# DRV8825.net
KiCad netlist of a schematic drawn in EAGLE
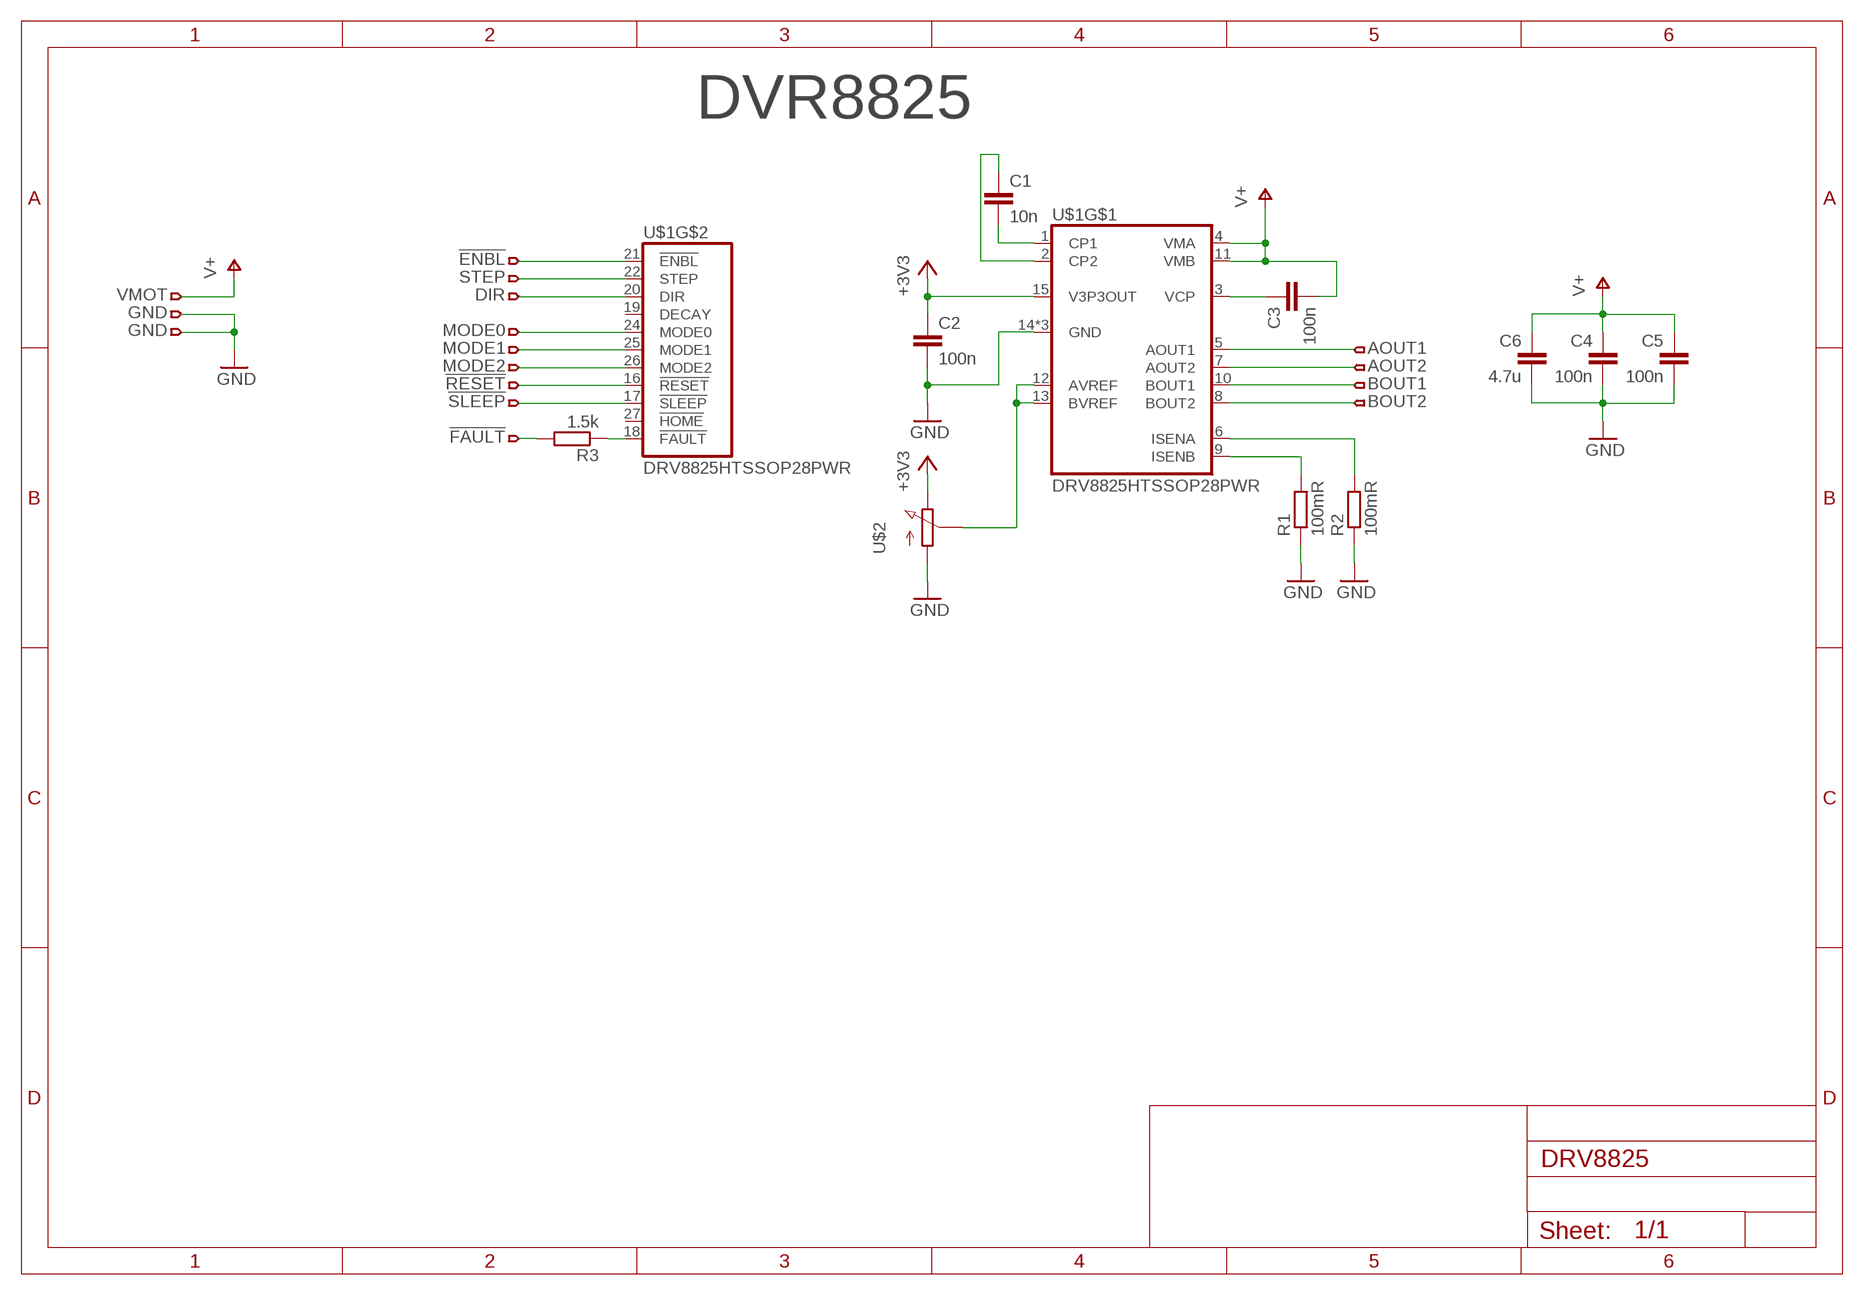
[diagram p0: schematic, sheet 1]

(export (version "E")
  (design (tool "Eeschema 10.0.6"))
  (components
    (comp (ref "C1")
      (value "10n")
      (footprint "eagle-import:C0603")
      (libsource (lib "eagle-import") (part "C-EUC0603"))
    )
    (comp (ref "C2")
      (value "100n")
      (footprint "eagle-import:C0603")
      (libsource (lib "eagle-import") (part "C-EUC0603"))
    )
    (comp (ref "C3")
      (value "100n")
      (footprint "eagle-import:C0603")
      (libsource (lib "eagle-import") (part "C-EUC0603"))
    )
    (comp (ref "C4")
      (value "100n")
      (footprint "eagle-import:C0603")
      (libsource (lib "eagle-import") (part "C-EUC0603"))
    )
    (comp (ref "C5")
      (value "100n")
      (footprint "eagle-import:C0603")
      (libsource (lib "eagle-import") (part "C-EUC0603"))
    )
    (comp (ref "C6")
      (value "4.7u")
      (footprint "eagle-import:C0603")
      (libsource (lib "eagle-import") (part "C-EUC0603"))
    )
    (comp (ref "JP3")
      (value "AOUT1")
      (footprint "eagle-import:1X01")
      (libsource (lib "eagle-import") (part "PINHD-1X1_2.54"))
    )
    (comp (ref "JP4")
      (value "AOUT2")
      (footprint "eagle-import:1X01")
      (libsource (lib "eagle-import") (part "PINHD-1X1_2.54"))
    )
    (comp (ref "JP5")
      (value "BOUT1")
      (footprint "eagle-import:1X01")
      (libsource (lib "eagle-import") (part "PINHD-1X1_2.54"))
    )
    (comp (ref "JP6")
      (value "BOUT2")
      (footprint "eagle-import:1X01")
      (libsource (lib "eagle-import") (part "PINHD-1X1_2.54"))
    )
    (comp (ref "JP7")
      (value "!ENBL")
      (footprint "eagle-import:1X01")
      (libsource (lib "eagle-import") (part "PINHD-1X1_2.54"))
    )
    (comp (ref "JP8")
      (value "STEP")
      (footprint "eagle-import:1X01")
      (libsource (lib "eagle-import") (part "PINHD-1X1_2.54"))
    )
    (comp (ref "JP9")
      (value "DIR")
      (footprint "eagle-import:1X01")
      (libsource (lib "eagle-import") (part "PINHD-1X1_2.54"))
    )
    (comp (ref "JP10")
      (value "VMOT")
      (footprint "eagle-import:1X01")
      (libsource (lib "eagle-import") (part "PINHD-1X1_2.54"))
    )
    (comp (ref "JP11")
      (value "MODE0")
      (footprint "eagle-import:1X01")
      (libsource (lib "eagle-import") (part "PINHD-1X1_2.54"))
    )
    (comp (ref "JP12")
      (value "MODE1")
      (footprint "eagle-import:1X01")
      (libsource (lib "eagle-import") (part "PINHD-1X1_2.54"))
    )
    (comp (ref "JP13")
      (value "MODE2")
      (footprint "eagle-import:1X01")
      (libsource (lib "eagle-import") (part "PINHD-1X1_2.54"))
    )
    (comp (ref "JP14")
      (value "!RESET")
      (footprint "eagle-import:1X01")
      (libsource (lib "eagle-import") (part "PINHD-1X1_2.54"))
    )
    (comp (ref "JP15")
      (value "!SLEEP")
      (footprint "eagle-import:1X01")
      (libsource (lib "eagle-import") (part "PINHD-1X1_2.54"))
    )
    (comp (ref "JP16")
      (value "GND")
      (footprint "eagle-import:1X01")
      (libsource (lib "eagle-import") (part "PINHD-1X1_2.54"))
    )
    (comp (ref "JP17")
      (value "!FAULT")
      (footprint "eagle-import:1X01")
      (libsource (lib "eagle-import") (part "PINHD-1X1_2.54"))
    )
    (comp (ref "JP18")
      (value "GND")
      (footprint "eagle-import:1X01")
      (libsource (lib "eagle-import") (part "PINHD-1X1_2.54"))
    )
    (comp (ref "R1")
      (value "100mR")
      (footprint "eagle-import:R0603")
      (libsource (lib "eagle-import") (part "R-EU_R0603"))
    )
    (comp (ref "R2")
      (value "100mR")
      (footprint "eagle-import:R0603")
      (libsource (lib "eagle-import") (part "R-EU_R0603"))
    )
    (comp (ref "R3")
      (value "1.5k")
      (footprint "eagle-import:R0603")
      (libsource (lib "eagle-import") (part "R-EU_R0603"))
    )
    (comp (ref "U$1")
      (value "DRV8825HTSSOP28PWR")
      (footprint "eagle-import:HTSSOP28PWP")
      (libsource (lib "eagle-import") (part "DRV8825HTSSOP28PWR"))
    )
    (comp (ref "U$2")
      (value "POT-PVZ3A")
      (footprint "eagle-import:PVZ3A")
      (libsource (lib "eagle-import") (part "POT-PVZ3A"))
    )
  )
  (nets
    (net (code "1") (name "+3V3") (class "Default")
      (node (ref "C2") (pin "1") (pinfunction "1_1") (pintype "passive"))
      (node (ref "U$1") (pin "15") (pinfunction "V3P3OUT_15") (pintype "bidirectional"))
      (node (ref "U$2") (pin "P$3") (pinfunction "E_P$3") (pintype "passive"))
    )
    (net (code "2") (name "GND") (class "Default")
      (node (ref "C2") (pin "2") (pinfunction "2_2") (pintype "passive"))
      (node (ref "C4") (pin "2") (pinfunction "2_2") (pintype "passive"))
      (node (ref "C5") (pin "2") (pinfunction "2_2") (pintype "passive"))
      (node (ref "C6") (pin "2") (pinfunction "2_2") (pintype "passive"))
      (node (ref "JP16") (pin "1") (pinfunction "PA0_1") (pintype "bidirectional"))
      (node (ref "JP18") (pin "1") (pinfunction "PA0_1") (pintype "bidirectional"))
      (node (ref "R1") (pin "1") (pinfunction "1_1") (pintype "passive"))
      (node (ref "R2") (pin "1") (pinfunction "1_1") (pintype "passive"))
      (node (ref "U$1") (pin "14") (pinfunction "GND_14") (pintype "bidirectional"))
      (node (ref "U$1") (pin "28") (pinfunction "GND_28") (pintype "bidirectional"))
      (node (ref "U$1") (pin "EXP") (pinfunction "GND_EXP") (pintype "bidirectional"))
      (node (ref "U$2") (pin "P$1") (pinfunction "A_P$1") (pintype "passive"))
    )
    (net (code "3") (name "Net-(JP3-PA0)") (class "Default")
      (node (ref "JP3") (pin "1") (pinfunction "PA0_1") (pintype "bidirectional"))
      (node (ref "U$1") (pin "5") (pinfunction "AOUT1_5") (pintype "bidirectional"))
    )
    (net (code "4") (name "Net-(JP4-PA0)") (class "Default")
      (node (ref "JP4") (pin "1") (pinfunction "PA0_1") (pintype "bidirectional"))
      (node (ref "U$1") (pin "7") (pinfunction "AOUT2_7") (pintype "bidirectional"))
    )
    (net (code "5") (name "Net-(JP5-PA0)") (class "Default")
      (node (ref "JP5") (pin "1") (pinfunction "PA0_1") (pintype "bidirectional"))
      (node (ref "U$1") (pin "10") (pinfunction "BOUT1_10") (pintype "bidirectional"))
    )
    (net (code "6") (name "Net-(JP6-PA0)") (class "Default")
      (node (ref "JP6") (pin "1") (pinfunction "PA0_1") (pintype "bidirectional"))
      (node (ref "U$1") (pin "8") (pinfunction "BOUT2_8") (pintype "bidirectional"))
    )
    (net (code "7") (name "Net-(JP7-PA0)") (class "Default")
      (node (ref "JP7") (pin "1") (pinfunction "PA0_1") (pintype "bidirectional"))
      (node (ref "U$1") (pin "21") (pinfunction "~{ENBL}_21") (pintype "bidirectional"))
    )
    (net (code "8") (name "Net-(JP8-PA0)") (class "Default")
      (node (ref "JP8") (pin "1") (pinfunction "PA0_1") (pintype "bidirectional"))
      (node (ref "U$1") (pin "22") (pinfunction "STEP_22") (pintype "bidirectional"))
    )
    (net (code "9") (name "Net-(JP9-PA0)") (class "Default")
      (node (ref "JP9") (pin "1") (pinfunction "PA0_1") (pintype "bidirectional"))
      (node (ref "U$1") (pin "20") (pinfunction "DIR_20") (pintype "bidirectional"))
    )
    (net (code "10") (name "Net-(JP11-PA0)") (class "Default")
      (node (ref "JP11") (pin "1") (pinfunction "PA0_1") (pintype "bidirectional"))
      (node (ref "U$1") (pin "24") (pinfunction "MODE0_24") (pintype "bidirectional"))
    )
    (net (code "11") (name "Net-(JP12-PA0)") (class "Default")
      (node (ref "JP12") (pin "1") (pinfunction "PA0_1") (pintype "bidirectional"))
      (node (ref "U$1") (pin "25") (pinfunction "MODE1_25") (pintype "bidirectional"))
    )
    (net (code "12") (name "Net-(JP13-PA0)") (class "Default")
      (node (ref "JP13") (pin "1") (pinfunction "PA0_1") (pintype "bidirectional"))
      (node (ref "U$1") (pin "26") (pinfunction "MODE2_26") (pintype "bidirectional"))
    )
    (net (code "13") (name "Net-(JP14-PA0)") (class "Default")
      (node (ref "JP14") (pin "1") (pinfunction "PA0_1") (pintype "bidirectional"))
      (node (ref "U$1") (pin "16") (pinfunction "~{RESET}_16") (pintype "bidirectional"))
    )
    (net (code "14") (name "Net-(JP15-PA0)") (class "Default")
      (node (ref "JP15") (pin "1") (pinfunction "PA0_1") (pintype "bidirectional"))
      (node (ref "U$1") (pin "17") (pinfunction "~{SLEEP}_17") (pintype "bidirectional"))
    )
    (net (code "15") (name "Net-(JP17-PA0)") (class "Default")
      (node (ref "JP17") (pin "1") (pinfunction "PA0_1") (pintype "bidirectional"))
      (node (ref "R3") (pin "2") (pinfunction "2_2") (pintype "passive"))
    )
    (net (code "16") (name "Net-(U$1A-AVREF)") (class "Default")
      (node (ref "U$1") (pin "12") (pinfunction "AVREF_12") (pintype "bidirectional"))
      (node (ref "U$1") (pin "13") (pinfunction "BVREF_13") (pintype "bidirectional"))
      (node (ref "U$2") (pin "P$2") (pinfunction "S_P$2") (pintype "passive"))
    )
    (net (code "17") (name "Net-(U$1A-CP1)") (class "Default")
      (node (ref "C1") (pin "2") (pinfunction "2_2") (pintype "passive"))
      (node (ref "U$1") (pin "1") (pinfunction "CP1_1") (pintype "bidirectional"))
    )
    (net (code "18") (name "Net-(U$1A-CP2)") (class "Default")
      (node (ref "C1") (pin "1") (pinfunction "1_1") (pintype "passive"))
      (node (ref "U$1") (pin "2") (pinfunction "CP2_2") (pintype "bidirectional"))
    )
    (net (code "19") (name "Net-(U$1A-ISENA)") (class "Default")
      (node (ref "R2") (pin "2") (pinfunction "2_2") (pintype "passive"))
      (node (ref "U$1") (pin "6") (pinfunction "ISENA_6") (pintype "bidirectional"))
    )
    (net (code "20") (name "Net-(U$1A-ISENB)") (class "Default")
      (node (ref "R1") (pin "2") (pinfunction "2_2") (pintype "passive"))
      (node (ref "U$1") (pin "9") (pinfunction "ISENB_9") (pintype "bidirectional"))
    )
    (net (code "21") (name "Net-(U$1A-VCP)") (class "Default")
      (node (ref "C3") (pin "1") (pinfunction "1_1") (pintype "passive"))
      (node (ref "U$1") (pin "3") (pinfunction "VCP_3") (pintype "bidirectional"))
    )
    (net (code "22") (name "Net-(U$1B-~{FAULT})") (class "Default")
      (node (ref "R3") (pin "1") (pinfunction "1_1") (pintype "passive"))
      (node (ref "U$1") (pin "18") (pinfunction "~{FAULT}_18") (pintype "bidirectional"))
    )
    (net (code "23") (name "V+") (class "Default")
      (node (ref "C3") (pin "2") (pinfunction "2_2") (pintype "passive"))
      (node (ref "C4") (pin "1") (pinfunction "1_1") (pintype "passive"))
      (node (ref "C5") (pin "1") (pinfunction "1_1") (pintype "passive"))
      (node (ref "C6") (pin "1") (pinfunction "1_1") (pintype "passive"))
      (node (ref "JP10") (pin "1") (pinfunction "PA0_1") (pintype "bidirectional"))
      (node (ref "U$1") (pin "11") (pinfunction "VMB_11") (pintype "bidirectional"))
      (node (ref "U$1") (pin "4") (pinfunction "VMA_4") (pintype "bidirectional"))
    )
    (net (code "24") (name "unconnected-(U$1B-DECAY-Pad19)") (class "Default")
      (node (ref "U$1") (pin "19") (pinfunction "DECAY_19") (pintype "bidirectional"))
    )
    (net (code "25") (name "unconnected-(U$1B-~{HOME}-Pad27)") (class "Default")
      (node (ref "U$1") (pin "27") (pinfunction "~{HOME}_27") (pintype "bidirectional"))
    )
  )
)
